# GPS.net
KiCad netlist of a schematic drawn in Altium Designer
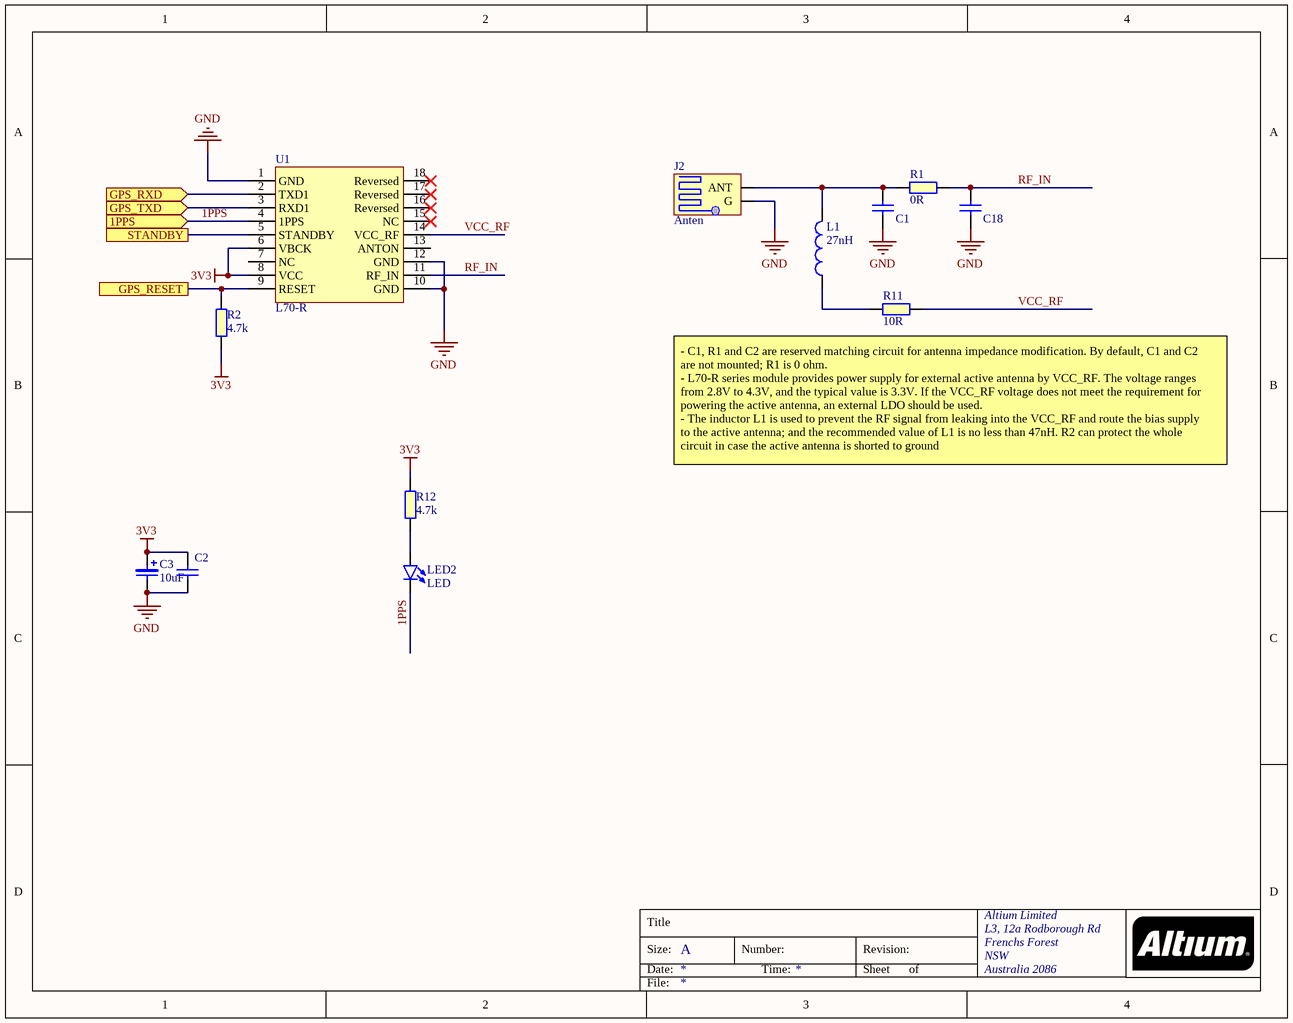
[diagram p0: GPS.SchDoc]

(export (version "E")
  (design (tool "Eeschema 10.0.6"))
  (components
    (comp (ref "C1") (value "DNP") (footprint "C_0603") (libsource (lib "Node") (part "CAP_0603")))
    (comp (ref "C2") (value "0.01uF") (footprint "C_0603") (libsource (lib "Node") (part "CAP_0603")))
    (comp (ref "C3")
      (value "10uF")
      (footprint "CASE A")
      (description "CAP TANT 10UF 16V 10% 2917")
      (fields (field (name "PART NUMBER") "T491A106K010AT") (field (name "VOLTAGE") "10VDC"))
      (libsource (lib "Node") (part "Capacitor-Tantalium"))
    )
    (comp (ref "C18") (value "DNP") (footprint "C_0603") (libsource (lib "Node") (part "CAP_0603")))
    (comp (ref "J2")
      (value "Anten")
      (footprint "ANTEN_IPEX")
      (description "CONN UMC RCPT STR 50 OHM SMD")
      (fields
        (field (name "MANUFACTURER") "Taoglas")
        (field (name "MANUFACTURER PART NUMBER") "RECE.20279.001E.01")
      )
      (libsource (lib "Node") (part "ANTEN_IPEX"))
    )
    (comp (ref "L1")
      (value "27nH")
      (footprint "INDUCTOR_0603")
      (libsource (lib "Node") (part "INDUCTOR_0603"))
    )
    (comp (ref "LED2") (value "LED") (footprint "LED_0603") (libsource (lib "Node") (part "LED_0603")))
    (comp (ref "R1") (value "0R") (footprint "R_0603") (libsource (lib "Node") (part "RES_0603")))
    (comp (ref "R2") (value "4.7k") (footprint "R_0603") (libsource (lib "") (part "RES_0603_1")))
    (comp (ref "R11") (value "10R") (footprint "R_0603") (libsource (lib "Node") (part "RES_0603")))
    (comp (ref "R12") (value "4.7k") (footprint "R_0603") (libsource (lib "") (part "RES_0603_1")))
    (comp (ref "U1")
      (value "L70-R")
      (footprint "MODULE_MAX-7Q")
      (description "GPS Receiver 1575.42MHz 2.5V/3.3V 18-Pin")
      (fields
        (field (name "MANUFACTURER") "Quectel Wireless Solutions")
        (field (name "MANUFACTURER PART NUMBER") "L70R")
      )
      (libsource (lib "Node") (part "L70-R"))
    )
  )
  (nets
    (net (code "1") (name "/1PPS") (class "Default")
      (node (ref "LED2") (pin "K") (pinfunction "K_K") (pintype "passive"))
      (node (ref "U1") (pin "4") (pinfunction "1PPS_4") (pintype "passive"))
    )
    (net (code "2") (name "/GPS_RESET") (class "Default")
      (node (ref "R2") (pin "2") (pinfunction "2_2") (pintype "passive"))
      (node (ref "U1") (pin "9") (pinfunction "RESET_9") (pintype "passive"))
    )
    (net (code "3") (name "/GPS_RXD") (class "Default")
      (node (ref "U1") (pin "2") (pinfunction "TXD1_2") (pintype "passive"))
    )
    (net (code "4") (name "/GPS_TXD") (class "Default")
      (node (ref "U1") (pin "3") (pinfunction "RXD1_3") (pintype "passive"))
    )
    (net (code "5") (name "/RF_IN") (class "Default")
      (node (ref "C18") (pin "1") (pinfunction "1_1") (pintype "passive"))
      (node (ref "R1") (pin "1") (pinfunction "1_1") (pintype "passive"))
      (node (ref "U1") (pin "11") (pinfunction "RF_IN_11") (pintype "passive"))
    )
    (net (code "6") (name "/STANDBY") (class "Default")
      (node (ref "U1") (pin "5") (pinfunction "STANDBY_5") (pintype "passive"))
    )
    (net (code "7") (name "/VCC_RF") (class "Default")
      (node (ref "R11") (pin "1") (pinfunction "1_1") (pintype "passive"))
      (node (ref "U1") (pin "14") (pinfunction "VCC_RF_14") (pintype "passive"))
    )
    (net (code "8") (name "3V3") (class "Default")
      (node (ref "C2") (pin "2") (pinfunction "2_2") (pintype "passive"))
      (node (ref "C3") (pin "A") (pinfunction "A_A") (pintype "passive"))
      (node (ref "R12") (pin "2") (pinfunction "2_2") (pintype "passive"))
      (node (ref "R2") (pin "1") (pinfunction "1_1") (pintype "passive"))
      (node (ref "U1") (pin "6") (pinfunction "VBCK_6") (pintype "passive"))
      (node (ref "U1") (pin "8") (pinfunction "VCC_8") (pintype "passive"))
    )
    (net (code "9") (name "GND") (class "Default")
      (node (ref "C1") (pin "2") (pinfunction "2_2") (pintype "passive"))
      (node (ref "C18") (pin "2") (pinfunction "2_2") (pintype "passive"))
      (node (ref "C2") (pin "1") (pinfunction "1_1") (pintype "passive"))
      (node (ref "C3") (pin "K") (pinfunction "K_K") (pintype "passive"))
      (node (ref "J2") (pin "2") (pinfunction "G_2") (pintype "passive"))
      (node (ref "U1") (pin "1") (pinfunction "GND_1") (pintype "passive"))
      (node (ref "U1") (pin "10") (pinfunction "GND_10") (pintype "passive"))
      (node (ref "U1") (pin "12") (pinfunction "GND_12") (pintype "passive"))
    )
    (net (code "10") (name "Net-(J2-ANT)") (class "Default")
      (node (ref "C1") (pin "1") (pinfunction "1_1") (pintype "passive"))
      (node (ref "J2") (pin "1") (pinfunction "ANT_1") (pintype "passive"))
      (node (ref "L1") (pin "2") (pinfunction "2_2") (pintype "passive"))
      (node (ref "R1") (pin "2") (pinfunction "2_2") (pintype "passive"))
    )
    (net (code "11") (name "Net-(L1-Pad1)") (class "Default")
      (node (ref "L1") (pin "1") (pinfunction "1_1") (pintype "passive"))
      (node (ref "R11") (pin "2") (pinfunction "2_2") (pintype "passive"))
    )
    (net (code "12") (name "Net-(LED2-PadA)") (class "Default")
      (node (ref "LED2") (pin "A") (pinfunction "A_A") (pintype "passive"))
      (node (ref "R12") (pin "1") (pinfunction "1_1") (pintype "passive"))
    )
    (net (code "13") (name "unconnected-(U1-ANTON-Pad13)") (class "Default")
      (node (ref "U1") (pin "13") (pinfunction "ANTON_13") (pintype "passive"))
    )
    (net (code "14") (name "unconnected-(U1-NC-Pad7)") (class "Default")
      (node (ref "U1") (pin "7") (pinfunction "NC_7") (pintype "passive"))
    )
    (net (code "15") (name "unconnected-(U1-NC-Pad15)") (class "Default")
      (node (ref "U1") (pin "15") (pinfunction "NC_15") (pintype "passive+no_connect"))
    )
    (net (code "16") (name "unconnected-(U1-Reversed-Pad16)") (class "Default")
      (node (ref "U1") (pin "16") (pinfunction "Reversed_16") (pintype "passive+no_connect"))
    )
    (net (code "17") (name "unconnected-(U1-Reversed-Pad17)") (class "Default")
      (node (ref "U1") (pin "17") (pinfunction "Reversed_17") (pintype "passive+no_connect"))
    )
    (net (code "18") (name "unconnected-(U1-Reversed-Pad18)") (class "Default")
      (node (ref "U1") (pin "18") (pinfunction "Reversed_18") (pintype "passive+no_connect"))
    )
  )
)
